# Servo_Control.net
KiCad netlist of a schematic drawn in EAGLE
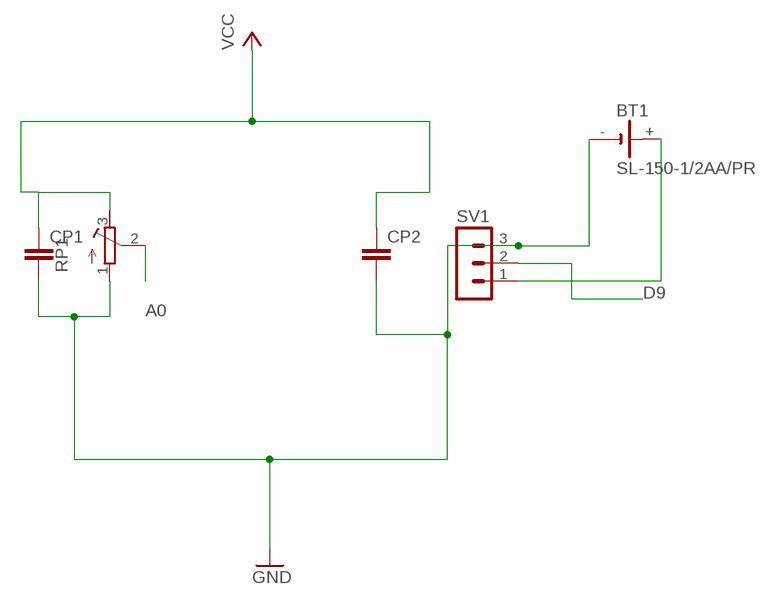
[diagram p0: schematic, sheet 1]

(export (version "E")
  (design (tool "Eeschema 10.0.6"))
  (components
    (comp (ref "BT1")
      (value "SL-150-1/2AA/PR")
      (footprint "eagle-import:SL-150-1_2AA_PR")
      (libsource (lib "eagle-import") (part "SL-150-1/2AA/PR"))
    )
    (comp (ref "CP1")
      (value "C2,5-3")
      (footprint "eagle-import:C2.5-3")
      (libsource (lib "eagle-import") (part "C2,5-3"))
    )
    (comp (ref "CP2")
      (value "C2,5-3")
      (footprint "eagle-import:C2.5-3")
      (libsource (lib "eagle-import") (part "C2,5-3"))
    )
    (comp (ref "RP1")
      (value "R-TRIMM4G/J")
      (footprint "eagle-import:RTRIM4G_J")
      (libsource (lib "eagle-import") (part "R-TRIMM4G/J"))
    )
    (comp (ref "SV1")
      (value "MA03-1")
      (footprint "eagle-import:MA03-1")
      (libsource (lib "eagle-import") (part "MA03-1"))
    )
  )
  (nets
    (net (code "1") (name "/A0") (class "Default")
      (node (ref "RP1") (pin "2") (pinfunction "S_2") (pintype "passive"))
    )
    (net (code "2") (name "/D9") (class "Default")
      (node (ref "SV1") (pin "2") (pinfunction "2_2") (pintype "passive"))
    )
    (net (code "3") (name "GND") (class "Default")
      (node (ref "BT1") (pin "-") (pinfunction "-_-") (pintype "passive"))
      (node (ref "CP1") (pin "2") (pinfunction "2_2") (pintype "passive"))
      (node (ref "CP2") (pin "2") (pinfunction "2_2") (pintype "passive"))
      (node (ref "RP1") (pin "1") (pinfunction "A_1") (pintype "passive"))
      (node (ref "SV1") (pin "3") (pinfunction "3_3") (pintype "passive"))
    )
    (net (code "4") (name "Net-(BT1-Pad+)") (class "Default")
      (node (ref "BT1") (pin "+") (pinfunction "+_+") (pintype "passive"))
      (node (ref "SV1") (pin "1") (pinfunction "1_1") (pintype "passive"))
    )
    (net (code "5") (name "VCC") (class "Default")
      (node (ref "CP1") (pin "1") (pinfunction "1_1") (pintype "passive"))
      (node (ref "CP2") (pin "1") (pinfunction "1_1") (pintype "passive"))
      (node (ref "RP1") (pin "3") (pinfunction "E_3") (pintype "passive"))
    )
  )
)
